# weaver_pot.net
KiCad netlist of a schematic drawn in EAGLE
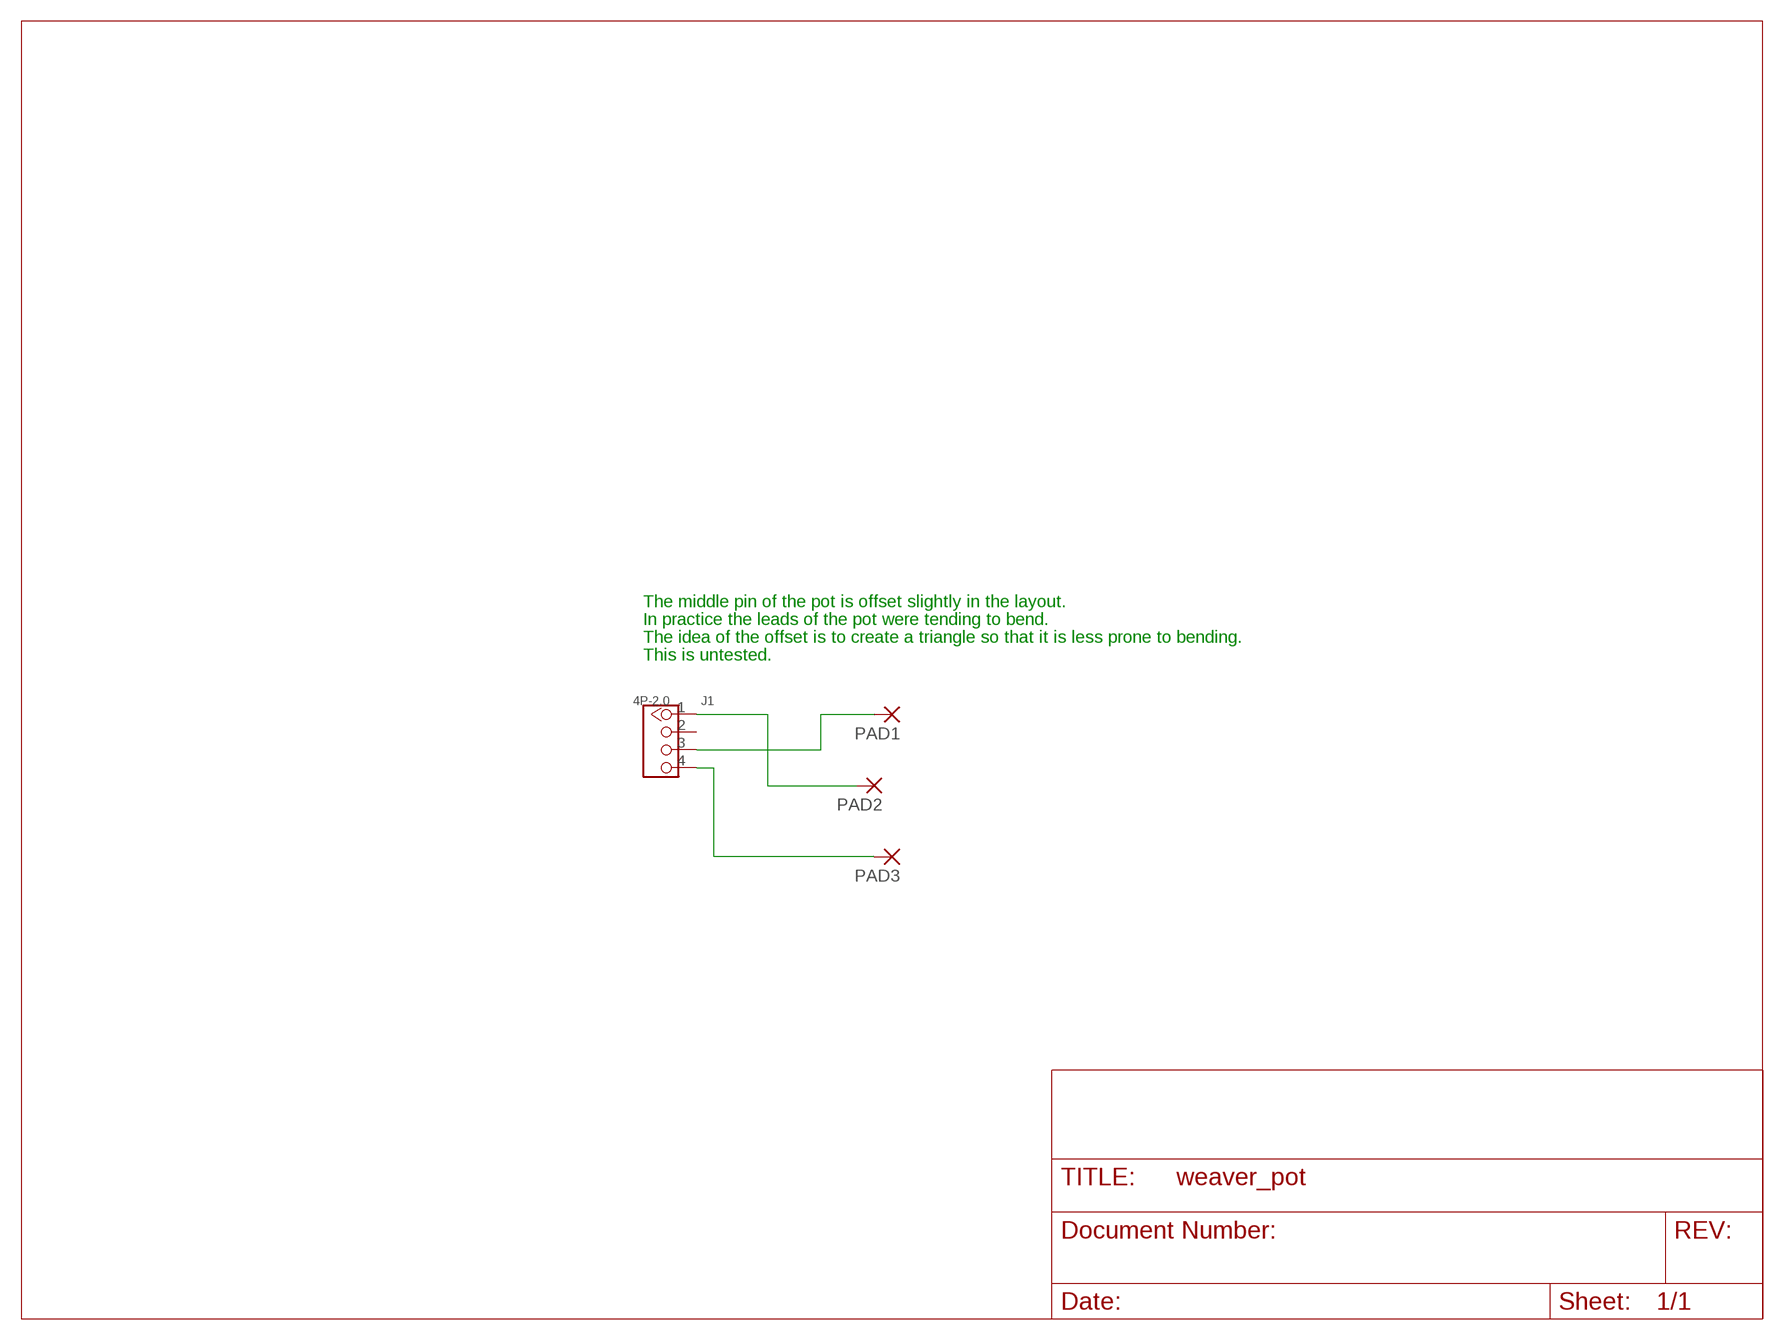
[diagram p0: schematic, sheet 1]

(export (version "E")
  (design (tool "Eeschema 10.0.6"))
  (components
    (comp (ref "J1")
      (value "4P-2.0")
      (footprint "eagle-import:HW4-2.0")
      (libsource (lib "eagle-import") (part "GROVE-CONNECTOR-DIP(4P-2.0)"))
    )
    (comp (ref "PAD1")
      (value "3,81/1,1")
      (footprint "eagle-import:3,81_1,1")
      (libsource (lib "eagle-import") (part "3,81/1,1"))
    )
    (comp (ref "PAD2")
      (value "3,81/1,1")
      (footprint "eagle-import:3,81_1,1")
      (libsource (lib "eagle-import") (part "3,81/1,1"))
    )
    (comp (ref "PAD3")
      (value "3,81/1,1")
      (footprint "eagle-import:3,81_1,1")
      (libsource (lib "eagle-import") (part "3,81/1,1"))
    )
  )
  (nets
    (net (code "1") (name "Net-(PAD1-P)") (class "Default")
      (node (ref "J1") (pin "3") (pinfunction "3_3") (pintype "bidirectional"))
      (node (ref "PAD1") (pin "1") (pinfunction "P_1") (pintype "passive"))
    )
    (net (code "2") (name "Net-(PAD2-P)") (class "Default")
      (node (ref "J1") (pin "1") (pinfunction "1_1") (pintype "bidirectional"))
      (node (ref "PAD2") (pin "1") (pinfunction "P_1") (pintype "passive"))
    )
    (net (code "3") (name "Net-(PAD3-P)") (class "Default")
      (node (ref "J1") (pin "4") (pinfunction "4_4") (pintype "bidirectional"))
      (node (ref "PAD3") (pin "1") (pinfunction "P_1") (pintype "passive"))
    )
    (net (code "4") (name "unconnected-(J1-Pad2)") (class "Default")
      (node (ref "J1") (pin "2") (pinfunction "2_2") (pintype "bidirectional"))
    )
  )
)
